# ECSE_Comp.net
KiCad netlist of a schematic drawn in Altium Designer
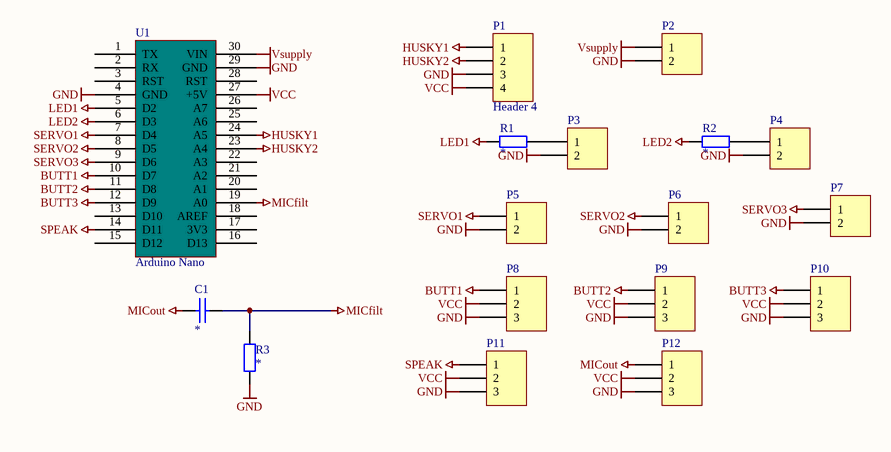
[diagram p0: ECSE_Comp.SchDoc]

(export (version "E")
  (design (tool "Eeschema 10.0.6"))
  (components
    (comp (ref "C1")
      (value "*")
      (footprint "CCAP-5P0")
      (description "TH ceramic capacitor with 5mm pitch")
      (libsource (lib "EE209_Library") (part "CerCap_TH_5P0"))
    )
    (comp (ref "P1")
      (value "Header 4")
      (footprint "ece-HDR1X4")
      (description "Header, 4-Pin")
      (fields (field (name "PUBLISHER") "Altium Limited"))
      (libsource (lib "ece components") (part "Header 4"))
    )
    (comp (ref "P2")
      (value "Header 2")
      (footprint "ece-HDR1X2")
      (description "Header, 2-Pin")
      (fields (field (name "PUBLISHER") "Altium Limited"))
      (libsource (lib "ece components") (part "Header 2"))
    )
    (comp (ref "P3")
      (value "Header 2")
      (footprint "ece-HDR1X2")
      (description "Header, 2-Pin")
      (fields (field (name "PUBLISHER") "Altium Limited"))
      (libsource (lib "ece components") (part "Header 2"))
    )
    (comp (ref "P4")
      (value "Header 2")
      (footprint "ece-HDR1X2")
      (description "Header, 2-Pin")
      (fields (field (name "PUBLISHER") "Altium Limited"))
      (libsource (lib "ece components") (part "Header 2"))
    )
    (comp (ref "P5")
      (value "Header 2")
      (footprint "ece-HDR1X2")
      (description "Header, 2-Pin")
      (fields (field (name "PUBLISHER") "Altium Limited"))
      (libsource (lib "ece components") (part "Header 2"))
    )
    (comp (ref "P6")
      (value "Header 2")
      (footprint "ece-HDR1X2")
      (description "Header, 2-Pin")
      (fields (field (name "PUBLISHER") "Altium Limited"))
      (libsource (lib "ece components") (part "Header 2"))
    )
    (comp (ref "P7")
      (value "Header 2")
      (footprint "ece-HDR1X2")
      (description "Header, 2-Pin")
      (fields (field (name "PUBLISHER") "Altium Limited"))
      (libsource (lib "ece components") (part "Header 2"))
    )
    (comp (ref "P8")
      (value "Header 3")
      (footprint "ece-HDR1X3")
      (description "Header, 3-Pin")
      (fields (field (name "PUBLISHER") "Altium Limited"))
      (libsource (lib "ece components") (part "Header 3"))
    )
    (comp (ref "P9")
      (value "Header 3")
      (footprint "ece-HDR1X3")
      (description "Header, 3-Pin")
      (fields (field (name "PUBLISHER") "Altium Limited"))
      (libsource (lib "ece components") (part "Header 3"))
    )
    (comp (ref "P10")
      (value "Header 3")
      (footprint "ece-HDR1X3")
      (description "Header, 3-Pin")
      (fields (field (name "PUBLISHER") "Altium Limited"))
      (libsource (lib "ece components") (part "Header 3"))
    )
    (comp (ref "P11")
      (value "Header 3")
      (footprint "ece-HDR1X3")
      (description "Header, 3-Pin")
      (fields (field (name "PUBLISHER") "Altium Limited"))
      (libsource (lib "ece components") (part "Header 3"))
    )
    (comp (ref "P12")
      (value "Header 3")
      (footprint "ece-HDR1X3")
      (description "Header, 3-Pin")
      (fields (field (name "PUBLISHER") "Altium Limited"))
      (libsource (lib "ece components") (part "Header 3"))
    )
    (comp (ref "R1")
      (value "*")
      (footprint "AXIAL-0.4")
      (description "Through hole resistor")
      (fields (field (name "PUBLISHER") "Altium Limited"))
      (libsource (lib "EE209_Library") (part "Res_TH_0AX4"))
    )
    (comp (ref "R2")
      (value "*")
      (footprint "AXIAL-0.4")
      (description "Through hole resistor")
      (fields (field (name "PUBLISHER") "Altium Limited"))
      (libsource (lib "EE209_Library") (part "Res_TH_0AX4"))
    )
    (comp (ref "R3")
      (value "*")
      (footprint "AXIAL-0.4")
      (description "Through hole resistor")
      (fields (field (name "PUBLISHER") "Altium Limited"))
      (libsource (lib "") (part "Res_TH_0AX4_1"))
    )
    (comp (ref "U1")
      (value "Arduino Nano")
      (footprint "PCBComponent_1")
      (libsource (lib "Nano") (part "Component_1"))
    )
  )
  (nets
    (net (code "1") (name "BUTT1") (class "Default")
      (node (ref "P8") (pin "1") (pinfunction "1_1") (pintype "passive"))
      (node (ref "U1") (pin "10") (pinfunction "D7_10") (pintype "passive"))
    )
    (net (code "2") (name "BUTT2") (class "Default")
      (node (ref "P9") (pin "1") (pinfunction "1_1") (pintype "passive"))
      (node (ref "U1") (pin "11") (pinfunction "D8_11") (pintype "passive"))
    )
    (net (code "3") (name "BUTT3") (class "Default")
      (node (ref "P10") (pin "1") (pinfunction "1_1") (pintype "passive"))
      (node (ref "U1") (pin "12") (pinfunction "D9_12") (pintype "passive"))
    )
    (net (code "4") (name "GND") (class "Default")
      (node (ref "P1") (pin "3") (pinfunction "3_3") (pintype "passive"))
      (node (ref "P10") (pin "3") (pinfunction "3_3") (pintype "passive"))
      (node (ref "P11") (pin "3") (pinfunction "3_3") (pintype "passive"))
      (node (ref "P12") (pin "3") (pinfunction "3_3") (pintype "passive"))
      (node (ref "P2") (pin "2") (pinfunction "2_2") (pintype "passive"))
      (node (ref "P3") (pin "2") (pinfunction "2_2") (pintype "passive"))
      (node (ref "P4") (pin "2") (pinfunction "2_2") (pintype "passive"))
      (node (ref "P5") (pin "2") (pinfunction "2_2") (pintype "passive"))
      (node (ref "P6") (pin "2") (pinfunction "2_2") (pintype "passive"))
      (node (ref "P7") (pin "2") (pinfunction "2_2") (pintype "passive"))
      (node (ref "P8") (pin "3") (pinfunction "3_3") (pintype "passive"))
      (node (ref "P9") (pin "3") (pinfunction "3_3") (pintype "passive"))
      (node (ref "R3") (pin "1") (pinfunction "1_1") (pintype "passive"))
      (node (ref "U1") (pin "29") (pinfunction "GND_29") (pintype "passive"))
      (node (ref "U1") (pin "4") (pinfunction "GND_4") (pintype "passive"))
    )
    (net (code "5") (name "HUSKY1") (class "Default")
      (node (ref "P1") (pin "1") (pinfunction "1_1") (pintype "passive"))
      (node (ref "U1") (pin "24") (pinfunction "A5_24") (pintype "passive"))
    )
    (net (code "6") (name "HUSKY2") (class "Default")
      (node (ref "P1") (pin "2") (pinfunction "2_2") (pintype "passive"))
      (node (ref "U1") (pin "23") (pinfunction "A4_23") (pintype "passive"))
    )
    (net (code "7") (name "LED1") (class "Default")
      (node (ref "R1") (pin "1") (pinfunction "1_1") (pintype "passive"))
      (node (ref "U1") (pin "5") (pinfunction "D2_5") (pintype "passive"))
    )
    (net (code "8") (name "LED2") (class "Default")
      (node (ref "R2") (pin "1") (pinfunction "1_1") (pintype "passive"))
      (node (ref "U1") (pin "6") (pinfunction "D3_6") (pintype "passive"))
    )
    (net (code "9") (name "MICfilt") (class "Default")
      (node (ref "C1") (pin "2") (pinfunction "2_2") (pintype "passive"))
      (node (ref "R3") (pin "2") (pinfunction "2_2") (pintype "passive"))
      (node (ref "U1") (pin "19") (pinfunction "A0_19") (pintype "passive"))
    )
    (net (code "10") (name "MICout") (class "Default")
      (node (ref "C1") (pin "1") (pinfunction "1_1") (pintype "passive"))
      (node (ref "P12") (pin "1") (pinfunction "1_1") (pintype "passive"))
    )
    (net (code "11") (name "Net-(P3-Pad1)") (class "Default")
      (node (ref "P3") (pin "1") (pinfunction "1_1") (pintype "passive"))
      (node (ref "R1") (pin "2") (pinfunction "2_2") (pintype "passive"))
    )
    (net (code "12") (name "Net-(P4-Pad1)") (class "Default")
      (node (ref "P4") (pin "1") (pinfunction "1_1") (pintype "passive"))
      (node (ref "R2") (pin "2") (pinfunction "2_2") (pintype "passive"))
    )
    (net (code "13") (name "SERVO1") (class "Default")
      (node (ref "P5") (pin "1") (pinfunction "1_1") (pintype "passive"))
      (node (ref "U1") (pin "7") (pinfunction "D4_7") (pintype "passive"))
    )
    (net (code "14") (name "SERVO2") (class "Default")
      (node (ref "P6") (pin "1") (pinfunction "1_1") (pintype "passive"))
      (node (ref "U1") (pin "8") (pinfunction "D5_8") (pintype "passive"))
    )
    (net (code "15") (name "SERVO3") (class "Default")
      (node (ref "P7") (pin "1") (pinfunction "1_1") (pintype "passive"))
      (node (ref "U1") (pin "9") (pinfunction "D6_9") (pintype "passive"))
    )
    (net (code "16") (name "SPEAK") (class "Default")
      (node (ref "P11") (pin "1") (pinfunction "1_1") (pintype "passive"))
      (node (ref "U1") (pin "14") (pinfunction "D11_14") (pintype "passive"))
    )
    (net (code "17") (name "VCC") (class "Default")
      (node (ref "P1") (pin "4") (pinfunction "4_4") (pintype "passive"))
      (node (ref "P10") (pin "2") (pinfunction "2_2") (pintype "passive"))
      (node (ref "P11") (pin "2") (pinfunction "2_2") (pintype "passive"))
      (node (ref "P12") (pin "2") (pinfunction "2_2") (pintype "passive"))
      (node (ref "P8") (pin "2") (pinfunction "2_2") (pintype "passive"))
      (node (ref "P9") (pin "2") (pinfunction "2_2") (pintype "passive"))
      (node (ref "U1") (pin "27") (pinfunction "+5V_27") (pintype "passive"))
    )
    (net (code "18") (name "Vsupply") (class "Default")
      (node (ref "P2") (pin "1") (pinfunction "1_1") (pintype "passive"))
      (node (ref "U1") (pin "30") (pinfunction "VIN_30") (pintype "passive"))
    )
    (net (code "19") (name "unconnected-(U1-3V3-Pad17)") (class "Default")
      (node (ref "U1") (pin "17") (pinfunction "3V3_17") (pintype "passive"))
    )
    (net (code "20") (name "unconnected-(U1-A1-Pad20)") (class "Default")
      (node (ref "U1") (pin "20") (pinfunction "A1_20") (pintype "passive"))
    )
    (net (code "21") (name "unconnected-(U1-A2-Pad21)") (class "Default")
      (node (ref "U1") (pin "21") (pinfunction "A2_21") (pintype "passive"))
    )
    (net (code "22") (name "unconnected-(U1-A3-Pad22)") (class "Default")
      (node (ref "U1") (pin "22") (pinfunction "A3_22") (pintype "passive"))
    )
    (net (code "23") (name "unconnected-(U1-A6-Pad25)") (class "Default")
      (node (ref "U1") (pin "25") (pinfunction "A6_25") (pintype "passive"))
    )
    (net (code "24") (name "unconnected-(U1-A7-Pad26)") (class "Default")
      (node (ref "U1") (pin "26") (pinfunction "A7_26") (pintype "passive"))
    )
    (net (code "25") (name "unconnected-(U1-AREF-Pad18)") (class "Default")
      (node (ref "U1") (pin "18") (pinfunction "AREF_18") (pintype "passive"))
    )
    (net (code "26") (name "unconnected-(U1-D10-Pad13)") (class "Default")
      (node (ref "U1") (pin "13") (pinfunction "D10_13") (pintype "passive"))
    )
    (net (code "27") (name "unconnected-(U1-D12-Pad15)") (class "Default")
      (node (ref "U1") (pin "15") (pinfunction "D12_15") (pintype "passive"))
    )
    (net (code "28") (name "unconnected-(U1-D13-Pad16)") (class "Default")
      (node (ref "U1") (pin "16") (pinfunction "D13_16") (pintype "passive"))
    )
    (net (code "29") (name "unconnected-(U1-RST-Pad3)") (class "Default")
      (node (ref "U1") (pin "3") (pinfunction "RST_3") (pintype "passive"))
    )
    (net (code "30") (name "unconnected-(U1-RST-Pad28)") (class "Default")
      (node (ref "U1") (pin "28") (pinfunction "RST_28") (pintype "passive"))
    )
    (net (code "31") (name "unconnected-(U1-RX-Pad2)") (class "Default")
      (node (ref "U1") (pin "2") (pinfunction "RX_2") (pintype "passive"))
    )
    (net (code "32") (name "unconnected-(U1-TX-Pad1)") (class "Default")
      (node (ref "U1") (pin "1") (pinfunction "TX_1") (pintype "passive"))
    )
  )
)
